# Sheet1.net
KiCad netlist of a schematic drawn in Altium Designer
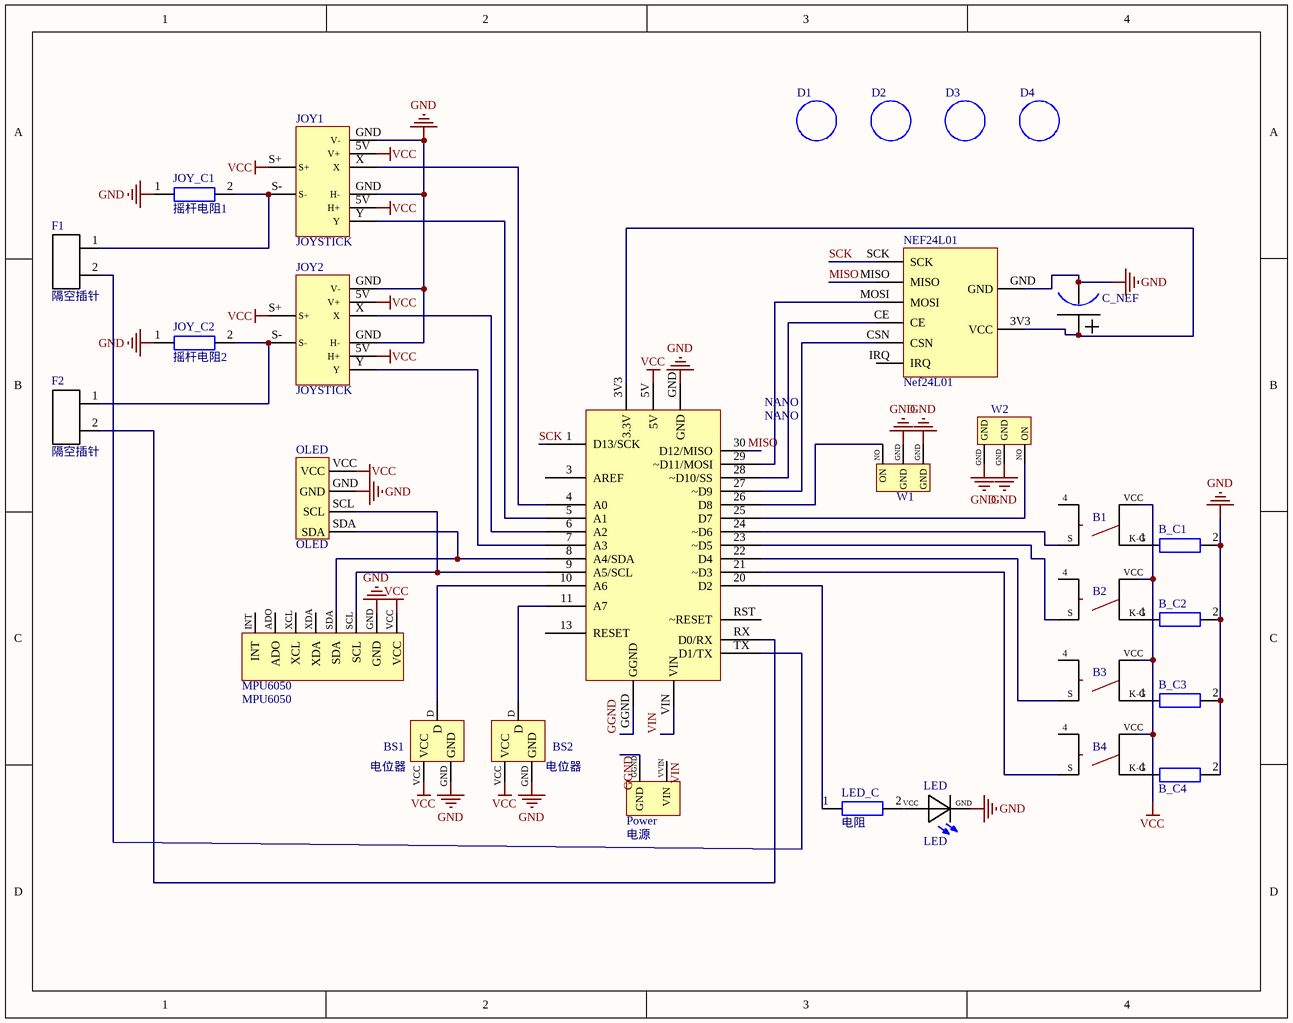
[diagram p0: Sheet1.SchDoc]

(export (version "E")
  (design (tool "Eeschema 10.0.6"))
  (components
    (comp (ref "B1")
      (value "按键开关")
      (footprint "按键开关")
      (description "自复位")
      (libsource (lib "Schlib1") (part "按键开关"))
    )
    (comp (ref "B2")
      (value "按键开关")
      (footprint "按键开关")
      (description "自复位")
      (libsource (lib "Schlib1") (part "按键开关"))
    )
    (comp (ref "B3")
      (value "按键开关")
      (footprint "按键开关")
      (description "自复位")
      (libsource (lib "Schlib1") (part "按键开关"))
    )
    (comp (ref "B4")
      (value "按键开关")
      (footprint "按键开关")
      (description "自复位")
      (libsource (lib "Schlib1") (part "按键开关"))
    )
    (comp (ref "BS1")
      (value "电位器")
      (footprint "WH148")
      (description "S/V/G")
      (libsource (lib "Schlib1") (part "电位器"))
    )
    (comp (ref "BS2")
      (value "电位器")
      (footprint "WH148")
      (description "S/V/G")
      (libsource (lib "Schlib1") (part "电位器"))
    )
    (comp (ref "B_C1") (value "电阻") (footprint "0805") (libsource (lib "Schlib1") (part "电阻")))
    (comp (ref "B_C2") (value "电阻") (footprint "0805") (libsource (lib "Schlib1") (part "电阻")))
    (comp (ref "B_C3") (value "电阻") (footprint "0805") (libsource (lib "Schlib1") (part "电阻")))
    (comp (ref "B_C4") (value "电阻") (footprint "0805") (libsource (lib "Schlib1") (part "电阻")))
    (comp (ref "C_NEF") (value "电容") (footprint "电容") (libsource (lib "Schlib1") (part "电容")))
    (comp (ref "D1") (value "定位孔") (footprint "散热孔") (libsource (lib "Schlib1") (part "定位孔")))
    (comp (ref "D2") (value "定位孔") (footprint "散热孔") (libsource (lib "Schlib1") (part "定位孔")))
    (comp (ref "D3") (value "定位孔") (footprint "散热孔") (libsource (lib "Schlib1") (part "定位孔")))
    (comp (ref "D4") (value "定位孔") (footprint "散热孔") (libsource (lib "Schlib1") (part "定位孔")))
    (comp (ref "F1") (value "隔空插针") (footprint "跳线帽") (libsource (lib "Schlib1") (part "隔空插针")))
    (comp (ref "F2") (value "隔空插针") (footprint "跳线帽") (libsource (lib "Schlib1") (part "隔空插针")))
    (comp (ref "JOY1")
      (value "JOYSTICK")
      (footprint "摇杆")
      (description "PS摇杆")
      (libsource (lib "Schlib1") (part "JOYSTICK"))
    )
    (comp (ref "JOY2")
      (value "JOYSTICK")
      (footprint "摇杆")
      (description "PS摇杆")
      (libsource (lib "Schlib1") (part "JOYSTICK"))
    )
    (comp (ref "JOY_C1") (value "摇杆电阻1") (footprint "0805") (libsource (lib "Schlib1") (part "电阻")))
    (comp (ref "JOY_C2") (value "摇杆电阻2") (footprint "0805") (libsource (lib "Schlib1") (part "电阻")))
    (comp (ref "LED") (value "LED") (footprint "1206") (libsource (lib "Schlib1") (part "LED")))
    (comp (ref "LED_C") (value "电阻") (footprint "0805") (libsource (lib "Schlib1") (part "电阻")))
    (comp (ref "MPU6050")
      (value "MPU6050")
      (footprint "MPU6050")
      (description "加速度计")
      (libsource (lib "Schlib1") (part "MPU6050"))
    )
    (comp (ref "NANO")
      (value "NANO")
      (footprint "NANO")
      (description "Arduino")
      (libsource (lib "Schlib1") (part "NANO"))
    )
    (comp (ref "NEF24L01")
      (value "Nef24L01")
      (footprint "Nef24L01")
      (description "board")
      (libsource (lib "Schlib1") (part "Nef24L01"))
    )
    (comp (ref "OLED")
      (value "OLED")
      (footprint "OLED")
      (description "0.96")
      (libsource (lib "Schlib1") (part "OLED"))
    )
    (comp (ref "Power") (value "电源") (footprint "电源") (libsource (lib "Schlib1") (part "电源")))
    (comp (ref "W1") (value "拨动开关") (footprint "拨动开关") (libsource (lib "") (part "拨动开关_1")))
    (comp (ref "W2") (value "拨动开关") (footprint "拨动开关") (libsource (lib "Schlib1") (part "拨动开关")))
  )
  (nets
    (net (code "1") (name "/GGND") (class "Default")
      (node (ref "NANO") (pin "GGND") (pinfunction "GGND_GGND") (pintype "passive"))
      (node (ref "Power") (pin "GGND") (pinfunction "GND_GGND") (pintype "passive"))
    )
    (net (code "2") (name "/MISO") (class "Default")
      (node (ref "NANO") (pin "30") (pinfunction "D12/MISO_30") (pintype "passive"))
      (node (ref "NEF24L01") (pin "MISO") (pinfunction "MISO_MISO") (pintype "passive"))
    )
    (net (code "3") (name "/SCK") (class "Default")
      (node (ref "NANO") (pin "1") (pinfunction "D13/SCK_1") (pintype "passive"))
      (node (ref "NEF24L01") (pin "SCK") (pinfunction "SCK_SCK") (pintype "passive"))
    )
    (net (code "4") (name "/VIN") (class "Default")
      (node (ref "NANO") (pin "VIN") (pinfunction "VIN_VIN") (pintype "passive"))
      (node (ref "Power") (pin "VVIN") (pinfunction "VIN_VVIN") (pintype "passive"))
    )
    (net (code "5") (name "GND") (class "Default")
      (node (ref "BS1") (pin "GND") (pinfunction "GND_GND") (pintype "passive"))
      (node (ref "BS2") (pin "GND") (pinfunction "GND_GND") (pintype "passive"))
      (node (ref "B_C1") (pin "2") (pinfunction "2_2") (pintype "passive"))
      (node (ref "B_C2") (pin "2") (pinfunction "2_2") (pintype "passive"))
      (node (ref "B_C3") (pin "2") (pinfunction "2_2") (pintype "passive"))
      (node (ref "B_C4") (pin "2") (pinfunction "2_2") (pintype "passive"))
      (node (ref "C_NEF") (pin "GND") (pinfunction "2_GND") (pintype "passive"))
      (node (ref "JOY1") (pin "GND") (pinfunction "H-_GND") (pintype "passive"))
      (node (ref "JOY2") (pin "GND") (pinfunction "H-_GND") (pintype "passive"))
      (node (ref "JOY_C1") (pin "1") (pinfunction "1_1") (pintype "passive"))
      (node (ref "JOY_C2") (pin "1") (pinfunction "1_1") (pintype "passive"))
      (node (ref "LED") (pin "GND") (pinfunction "2_GND") (pintype "passive"))
      (node (ref "MPU6050") (pin "GND") (pinfunction "GND_GND") (pintype "passive"))
      (node (ref "NANO") (pin "GND") (pinfunction "GND_GND") (pintype "passive"))
      (node (ref "NEF24L01") (pin "GND") (pinfunction "GND_GND") (pintype "passive"))
      (node (ref "OLED") (pin "GND") (pinfunction "GND_GND") (pintype "passive"))
      (node (ref "W1") (pin "GND") (pinfunction "GND_GND") (pintype "passive"))
      (node (ref "W2") (pin "GND") (pinfunction "GND_GND") (pintype "passive"))
    )
    (net (code "6") (name "Net-(B1-1-PadK-G)") (class "Default")
      (node (ref "B1") (pin "K-G") (pinfunction "1_K-G") (pintype "passive"))
      (node (ref "B_C1") (pin "1") (pinfunction "1_1") (pintype "passive"))
    )
    (net (code "7") (name "Net-(B2-1-PadK-G)") (class "Default")
      (node (ref "B2") (pin "K-G") (pinfunction "1_K-G") (pintype "passive"))
      (node (ref "B_C2") (pin "1") (pinfunction "1_1") (pintype "passive"))
    )
    (net (code "8") (name "Net-(B3-1-PadK-G)") (class "Default")
      (node (ref "B3") (pin "K-G") (pinfunction "1_K-G") (pintype "passive"))
      (node (ref "B_C3") (pin "1") (pinfunction "1_1") (pintype "passive"))
    )
    (net (code "9") (name "Net-(B4-1-PadK-G)") (class "Default")
      (node (ref "B4") (pin "K-G") (pinfunction "1_K-G") (pintype "passive"))
      (node (ref "B_C4") (pin "1") (pinfunction "1_1") (pintype "passive"))
    )
    (net (code "10") (name "Net-(C_NEF-+)") (class "Default")
      (node (ref "C_NEF") (pin "3V3") (pinfunction "+_3V3") (pintype "passive"))
      (node (ref "NANO") (pin "3V3") (pinfunction "3.3V_3V3") (pintype "passive"))
      (node (ref "NEF24L01") (pin "3V3") (pinfunction "VCC_3V3") (pintype "passive"))
    )
    (net (code "11") (name "Net-(F1-Pad1)") (class "Default")
      (node (ref "F1") (pin "1") (pinfunction "1_1") (pintype "passive"))
      (node (ref "JOY1") (pin "S-") (pinfunction "S-_S-") (pintype "passive"))
      (node (ref "JOY_C1") (pin "2") (pinfunction "2_2") (pintype "passive"))
    )
    (net (code "12") (name "Net-(F2-Pad1)") (class "Default")
      (node (ref "F2") (pin "1") (pinfunction "1_1") (pintype "passive"))
      (node (ref "JOY2") (pin "S-") (pinfunction "S-_S-") (pintype "passive"))
      (node (ref "JOY_C2") (pin "2") (pinfunction "2_2") (pintype "passive"))
    )
    (net (code "13") (name "Net-(LED-1)") (class "Default")
      (node (ref "LED") (pin "VCC") (pinfunction "1_VCC") (pintype "passive"))
      (node (ref "LED_C") (pin "2") (pinfunction "2_2") (pintype "passive"))
    )
    (net (code "14") (name "Net-(NANO-A0)") (class "Default")
      (node (ref "JOY1") (pin "X") (pinfunction "X_X") (pintype "passive"))
      (node (ref "NANO") (pin "4") (pinfunction "A0_4") (pintype "passive"))
    )
    (net (code "15") (name "Net-(NANO-A1)") (class "Default")
      (node (ref "JOY1") (pin "Y") (pinfunction "Y_Y") (pintype "passive"))
      (node (ref "NANO") (pin "5") (pinfunction "A1_5") (pintype "passive"))
    )
    (net (code "16") (name "Net-(NANO-A2)") (class "Default")
      (node (ref "JOY2") (pin "X") (pinfunction "X_X") (pintype "passive"))
      (node (ref "NANO") (pin "6") (pinfunction "A2_6") (pintype "passive"))
    )
    (net (code "17") (name "Net-(NANO-A3)") (class "Default")
      (node (ref "JOY2") (pin "Y") (pinfunction "Y_Y") (pintype "passive"))
      (node (ref "NANO") (pin "7") (pinfunction "A3_7") (pintype "passive"))
    )
    (net (code "18") (name "Net-(NANO-A4{slash}SDA)") (class "Default")
      (node (ref "MPU6050") (pin "SDA") (pinfunction "SDA_SDA") (pintype "passive"))
      (node (ref "NANO") (pin "8") (pinfunction "A4/SDA_8") (pintype "passive"))
      (node (ref "OLED") (pin "SDA") (pinfunction "SDA_SDA") (pintype "passive"))
    )
    (net (code "19") (name "Net-(NANO-A5{slash}SCL)") (class "Default")
      (node (ref "MPU6050") (pin "SCL") (pinfunction "SCL_SCL") (pintype "passive"))
      (node (ref "NANO") (pin "9") (pinfunction "A5/SCL_9") (pintype "passive"))
      (node (ref "OLED") (pin "SCL") (pinfunction "SCL_SCL") (pintype "passive"))
    )
    (net (code "20") (name "Net-(NANO-A6)") (class "Default")
      (node (ref "BS1") (pin "D") (pinfunction "D_D") (pintype "passive"))
      (node (ref "NANO") (pin "10") (pinfunction "A6_10") (pintype "passive"))
    )
    (net (code "21") (name "Net-(NANO-A7)") (class "Default")
      (node (ref "BS2") (pin "D") (pinfunction "D_D") (pintype "passive"))
      (node (ref "NANO") (pin "11") (pinfunction "A7_11") (pintype "passive"))
    )
    (net (code "22") (name "Net-(NANO-D0{slash}RX)") (class "Default")
      (node (ref "F2") (pin "2") (pinfunction "2_2") (pintype "passive"))
      (node (ref "NANO") (pin "RX") (pinfunction "D0/RX_RX") (pintype "passive"))
    )
    (net (code "23") (name "Net-(NANO-D1{slash}TX)") (class "Default")
      (node (ref "F1") (pin "2") (pinfunction "2_2") (pintype "passive"))
      (node (ref "NANO") (pin "TX") (pinfunction "D1/TX_TX") (pintype "passive"))
    )
    (net (code "24") (name "Net-(NANO-D2)") (class "Default")
      (node (ref "LED_C") (pin "1") (pinfunction "1_1") (pintype "passive"))
      (node (ref "NANO") (pin "20") (pinfunction "D2_20") (pintype "passive"))
    )
    (net (code "25") (name "Net-(NANO-D4)") (class "Default")
      (node (ref "B3") (pin "S") (pinfunction "2_S") (pintype "passive"))
      (node (ref "NANO") (pin "22") (pinfunction "D4_22") (pintype "passive"))
    )
    (net (code "26") (name "Net-(NANO-D7)") (class "Default")
      (node (ref "NANO") (pin "25") (pinfunction "D7_25") (pintype "passive"))
      (node (ref "W2") (pin "NO") (pinfunction "ON_NO") (pintype "passive"))
    )
    (net (code "27") (name "Net-(NANO-D8)") (class "Default")
      (node (ref "NANO") (pin "26") (pinfunction "D8_26") (pintype "passive"))
      (node (ref "W1") (pin "NO") (pinfunction "ON_NO") (pintype "passive"))
    )
    (net (code "28") (name "Net-(NANO-~D3)") (class "Default")
      (node (ref "B4") (pin "S") (pinfunction "2_S") (pintype "passive"))
      (node (ref "NANO") (pin "21") (pinfunction "~D3_21") (pintype "passive"))
    )
    (net (code "29") (name "Net-(NANO-~D5)") (class "Default")
      (node (ref "B2") (pin "S") (pinfunction "2_S") (pintype "passive"))
      (node (ref "NANO") (pin "23") (pinfunction "~D5_23") (pintype "passive"))
    )
    (net (code "30") (name "Net-(NANO-~D6)") (class "Default")
      (node (ref "B1") (pin "S") (pinfunction "2_S") (pintype "passive"))
      (node (ref "NANO") (pin "24") (pinfunction "~D6_24") (pintype "passive"))
    )
    (net (code "31") (name "Net-(NANO-~D9)") (class "Default")
      (node (ref "NANO") (pin "27") (pinfunction "~D9_27") (pintype "passive"))
      (node (ref "NEF24L01") (pin "CSN") (pinfunction "CSN_CSN") (pintype "passive"))
    )
    (net (code "32") (name "Net-(NANO-~D10{slash}SS)") (class "Default")
      (node (ref "NANO") (pin "28") (pinfunction "~D10/SS_28") (pintype "passive"))
      (node (ref "NEF24L01") (pin "CE") (pinfunction "CE_CE") (pintype "passive"))
    )
    (net (code "33") (name "Net-(NANO-~D11{slash}MOSI)") (class "Default")
      (node (ref "NANO") (pin "29") (pinfunction "~D11/MOSI_29") (pintype "passive"))
      (node (ref "NEF24L01") (pin "MOSI") (pinfunction "MOSI_MOSI") (pintype "passive"))
    )
    (net (code "34") (name "VCC") (class "Default")
      (node (ref "B1") (pin "VCC") (pinfunction "1_VCC") (pintype "passive"))
      (node (ref "B2") (pin "VCC") (pinfunction "1_VCC") (pintype "passive"))
      (node (ref "B3") (pin "VCC") (pinfunction "1_VCC") (pintype "passive"))
      (node (ref "B4") (pin "VCC") (pinfunction "1_VCC") (pintype "passive"))
      (node (ref "BS1") (pin "VCC") (pinfunction "VCC_VCC") (pintype "passive"))
      (node (ref "BS2") (pin "VCC") (pinfunction "VCC_VCC") (pintype "passive"))
      (node (ref "JOY1") (pin "5V") (pinfunction "V+_5V") (pintype "passive"))
      (node (ref "JOY1") (pin "S+") (pinfunction "S+_S+") (pintype "passive"))
      (node (ref "JOY2") (pin "5V") (pinfunction "H+_5V") (pintype "passive"))
      (node (ref "JOY2") (pin "S+") (pinfunction "S+_S+") (pintype "passive"))
      (node (ref "MPU6050") (pin "VCC") (pinfunction "VCC_VCC") (pintype "passive"))
      (node (ref "NANO") (pin "5V") (pinfunction "5V_5V") (pintype "passive"))
      (node (ref "OLED") (pin "VCC") (pinfunction "VCC_VCC") (pintype "passive"))
    )
    (net (code "35") (name "unconnected-(B1-2-Pad4)") (class "Default")
      (node (ref "B1") (pin "4") (pinfunction "2_4") (pintype "passive"))
    )
    (net (code "36") (name "unconnected-(B2-2-Pad4)") (class "Default")
      (node (ref "B2") (pin "4") (pinfunction "2_4") (pintype "passive"))
    )
    (net (code "37") (name "unconnected-(B3-2-Pad4)") (class "Default")
      (node (ref "B3") (pin "4") (pinfunction "2_4") (pintype "passive"))
    )
    (net (code "38") (name "unconnected-(B4-2-Pad4)") (class "Default")
      (node (ref "B4") (pin "4") (pinfunction "2_4") (pintype "passive"))
    )
    (net (code "39") (name "unconnected-(MPU6050-PadADO)") (class "Default")
      (node (ref "MPU6050") (pin "ADO") (pinfunction "ADO_ADO") (pintype "passive"))
    )
    (net (code "40") (name "unconnected-(MPU6050-PadINT)") (class "Default")
      (node (ref "MPU6050") (pin "INT") (pinfunction "INT_INT") (pintype "passive"))
    )
    (net (code "41") (name "unconnected-(MPU6050-PadXCL)") (class "Default")
      (node (ref "MPU6050") (pin "XCL") (pinfunction "XCL_XCL") (pintype "passive"))
    )
    (net (code "42") (name "unconnected-(MPU6050-PadXDA)") (class "Default")
      (node (ref "MPU6050") (pin "XDA") (pinfunction "XDA_XDA") (pintype "passive"))
    )
    (net (code "43") (name "unconnected-(NANO-AREF-Pad3)") (class "Default")
      (node (ref "NANO") (pin "3") (pinfunction "AREF_3") (pintype "passive"))
    )
    (net (code "44") (name "unconnected-(NANO-RESET-Pad13)") (class "Default")
      (node (ref "NANO") (pin "13") (pinfunction "RESET_13") (pintype "passive"))
    )
    (net (code "45") (name "unconnected-(NANO-~RESET-PadRST)") (class "Default")
      (node (ref "NANO") (pin "RST") (pinfunction "~RESET_RST") (pintype "passive"))
    )
    (net (code "46") (name "unconnected-(NEF24L01-PadIRQ)") (class "Default")
      (node (ref "NEF24L01") (pin "IRQ") (pinfunction "IRQ_IRQ") (pintype "passive"))
    )
  )
)
